# Buck_Converters.net
KiCad netlist of a schematic drawn in Altium Designer
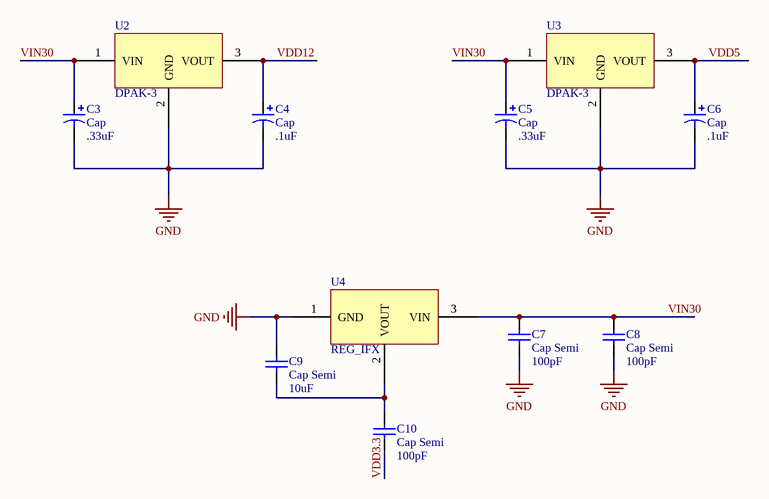
[diagram p0: Buck_Converters.SchDoc]

(export (version "E")
  (design (tool "Eeschema 10.0.6"))
  (components
    (comp (ref "C3")
      (value "Cap")
      (footprint "C0805")
      (description "Polarized Capacitor (Surface Mount)")
      (fields (field (name "ALTIUM_VALUE") ".33uF") (field (name "PUBLISHER") "Altium Limited"))
      (libsource (lib "Miscellaneous Devices") (part "Cap Pol3"))
    )
    (comp (ref "C4")
      (value "Cap")
      (footprint "C0805")
      (description "Polarized Capacitor (Surface Mount)")
      (fields (field (name "ALTIUM_VALUE") ".1uF") (field (name "PUBLISHER") "Altium Limited"))
      (libsource (lib "Miscellaneous Devices") (part "Cap Pol3"))
    )
    (comp (ref "C5")
      (value "Cap")
      (footprint "C0805")
      (description "Polarized Capacitor (Surface Mount)")
      (fields (field (name "ALTIUM_VALUE") ".33uF") (field (name "PUBLISHER") "Altium Limited"))
      (libsource (lib "Miscellaneous Devices") (part "Cap Pol3"))
    )
    (comp (ref "C6")
      (value "Cap")
      (footprint "C0805")
      (description "Polarized Capacitor (Surface Mount)")
      (fields (field (name "ALTIUM_VALUE") ".1uF") (field (name "PUBLISHER") "Altium Limited"))
      (libsource (lib "Miscellaneous Devices") (part "Cap Pol3"))
    )
    (comp (ref "C7")
      (value "Cap Semi")
      (footprint "C1206")
      (description "Capacitor (Semiconductor SIM Model)")
      (fields (field (name "ALTIUM_VALUE") "100pF") (field (name "PUBLISHER") "Altium Limited"))
      (libsource (lib "Miscellaneous Devices") (part "Cap Semi"))
    )
    (comp (ref "C8")
      (value "Cap Semi")
      (footprint "C1206")
      (description "Capacitor (Semiconductor SIM Model)")
      (fields (field (name "ALTIUM_VALUE") "100pF") (field (name "PUBLISHER") "Altium Limited"))
      (libsource (lib "Miscellaneous Devices") (part "Cap Semi"))
    )
    (comp (ref "C9")
      (value "Cap Semi")
      (footprint "C1206")
      (description "Capacitor (Semiconductor SIM Model)")
      (fields (field (name "ALTIUM_VALUE") "10uF") (field (name "PUBLISHER") "Altium Limited"))
      (libsource (lib "Miscellaneous Devices") (part "Cap Semi"))
    )
    (comp (ref "C10")
      (value "Cap Semi")
      (footprint "C1206")
      (description "Capacitor (Semiconductor SIM Model)")
      (fields (field (name "ALTIUM_VALUE") "100pF") (field (name "PUBLISHER") "Altium Limited"))
      (libsource (lib "Miscellaneous Devices") (part "Cap Semi"))
    )
    (comp (ref "U2") (value "DPAK-3") (footprint "DPAK-3") (libsource (lib "Reg_DPAK-3") (part "DPAK-3")))
    (comp (ref "U3") (value "DPAK-3") (footprint "DPAK-3") (libsource (lib "Reg_DPAK-3") (part "DPAK-3")))
    (comp (ref "U4") (value "REG_IFX") (footprint "Reg_IFX") (libsource (lib "Reg_IFX") (part "REG_IFX")))
  )
  (nets
    (net (code "1") (name "/VDD3.3") (class "Default")
      (node (ref "C10") (pin "1") (pinfunction "1_1") (pintype "passive"))
    )
    (net (code "2") (name "/VDD5") (class "Default")
      (node (ref "C6") (pin "1") (pinfunction "1_1") (pintype "passive"))
      (node (ref "U3") (pin "3") (pinfunction "VOUT_3") (pintype "passive"))
    )
    (net (code "3") (name "/VDD12") (class "Default")
      (node (ref "C4") (pin "1") (pinfunction "1_1") (pintype "passive"))
      (node (ref "U2") (pin "3") (pinfunction "VOUT_3") (pintype "passive"))
    )
    (net (code "4") (name "/VIN30") (class "Default")
      (node (ref "C3") (pin "1") (pinfunction "1_1") (pintype "passive"))
      (node (ref "C5") (pin "1") (pinfunction "1_1") (pintype "passive"))
      (node (ref "C7") (pin "2") (pinfunction "2_2") (pintype "passive"))
      (node (ref "C8") (pin "2") (pinfunction "2_2") (pintype "passive"))
      (node (ref "U2") (pin "1") (pinfunction "VIN_1") (pintype "passive"))
      (node (ref "U3") (pin "1") (pinfunction "VIN_1") (pintype "passive"))
      (node (ref "U4") (pin "3") (pinfunction "VIN_3") (pintype "passive"))
    )
    (net (code "5") (name "GND") (class "Default")
      (node (ref "C3") (pin "2") (pinfunction "2_2") (pintype "passive"))
      (node (ref "C4") (pin "2") (pinfunction "2_2") (pintype "passive"))
      (node (ref "C5") (pin "2") (pinfunction "2_2") (pintype "passive"))
      (node (ref "C6") (pin "2") (pinfunction "2_2") (pintype "passive"))
      (node (ref "C7") (pin "1") (pinfunction "1_1") (pintype "passive"))
      (node (ref "C8") (pin "1") (pinfunction "1_1") (pintype "passive"))
      (node (ref "C9") (pin "2") (pinfunction "2_2") (pintype "passive"))
      (node (ref "U2") (pin "2") (pinfunction "GND_2") (pintype "passive"))
      (node (ref "U3") (pin "2") (pinfunction "GND_2") (pintype "passive"))
      (node (ref "U4") (pin "1") (pinfunction "GND_1") (pintype "passive"))
    )
    (net (code "6") (name "Net-(U4-VOUT)") (class "Default")
      (node (ref "C10") (pin "2") (pinfunction "2_2") (pintype "passive"))
      (node (ref "C9") (pin "1") (pinfunction "1_1") (pintype "passive"))
      (node (ref "U4") (pin "2") (pinfunction "VOUT_2") (pintype "passive"))
    )
  )
)
